# Final_Schematic.net
KiCad netlist of a schematic drawn in EAGLE
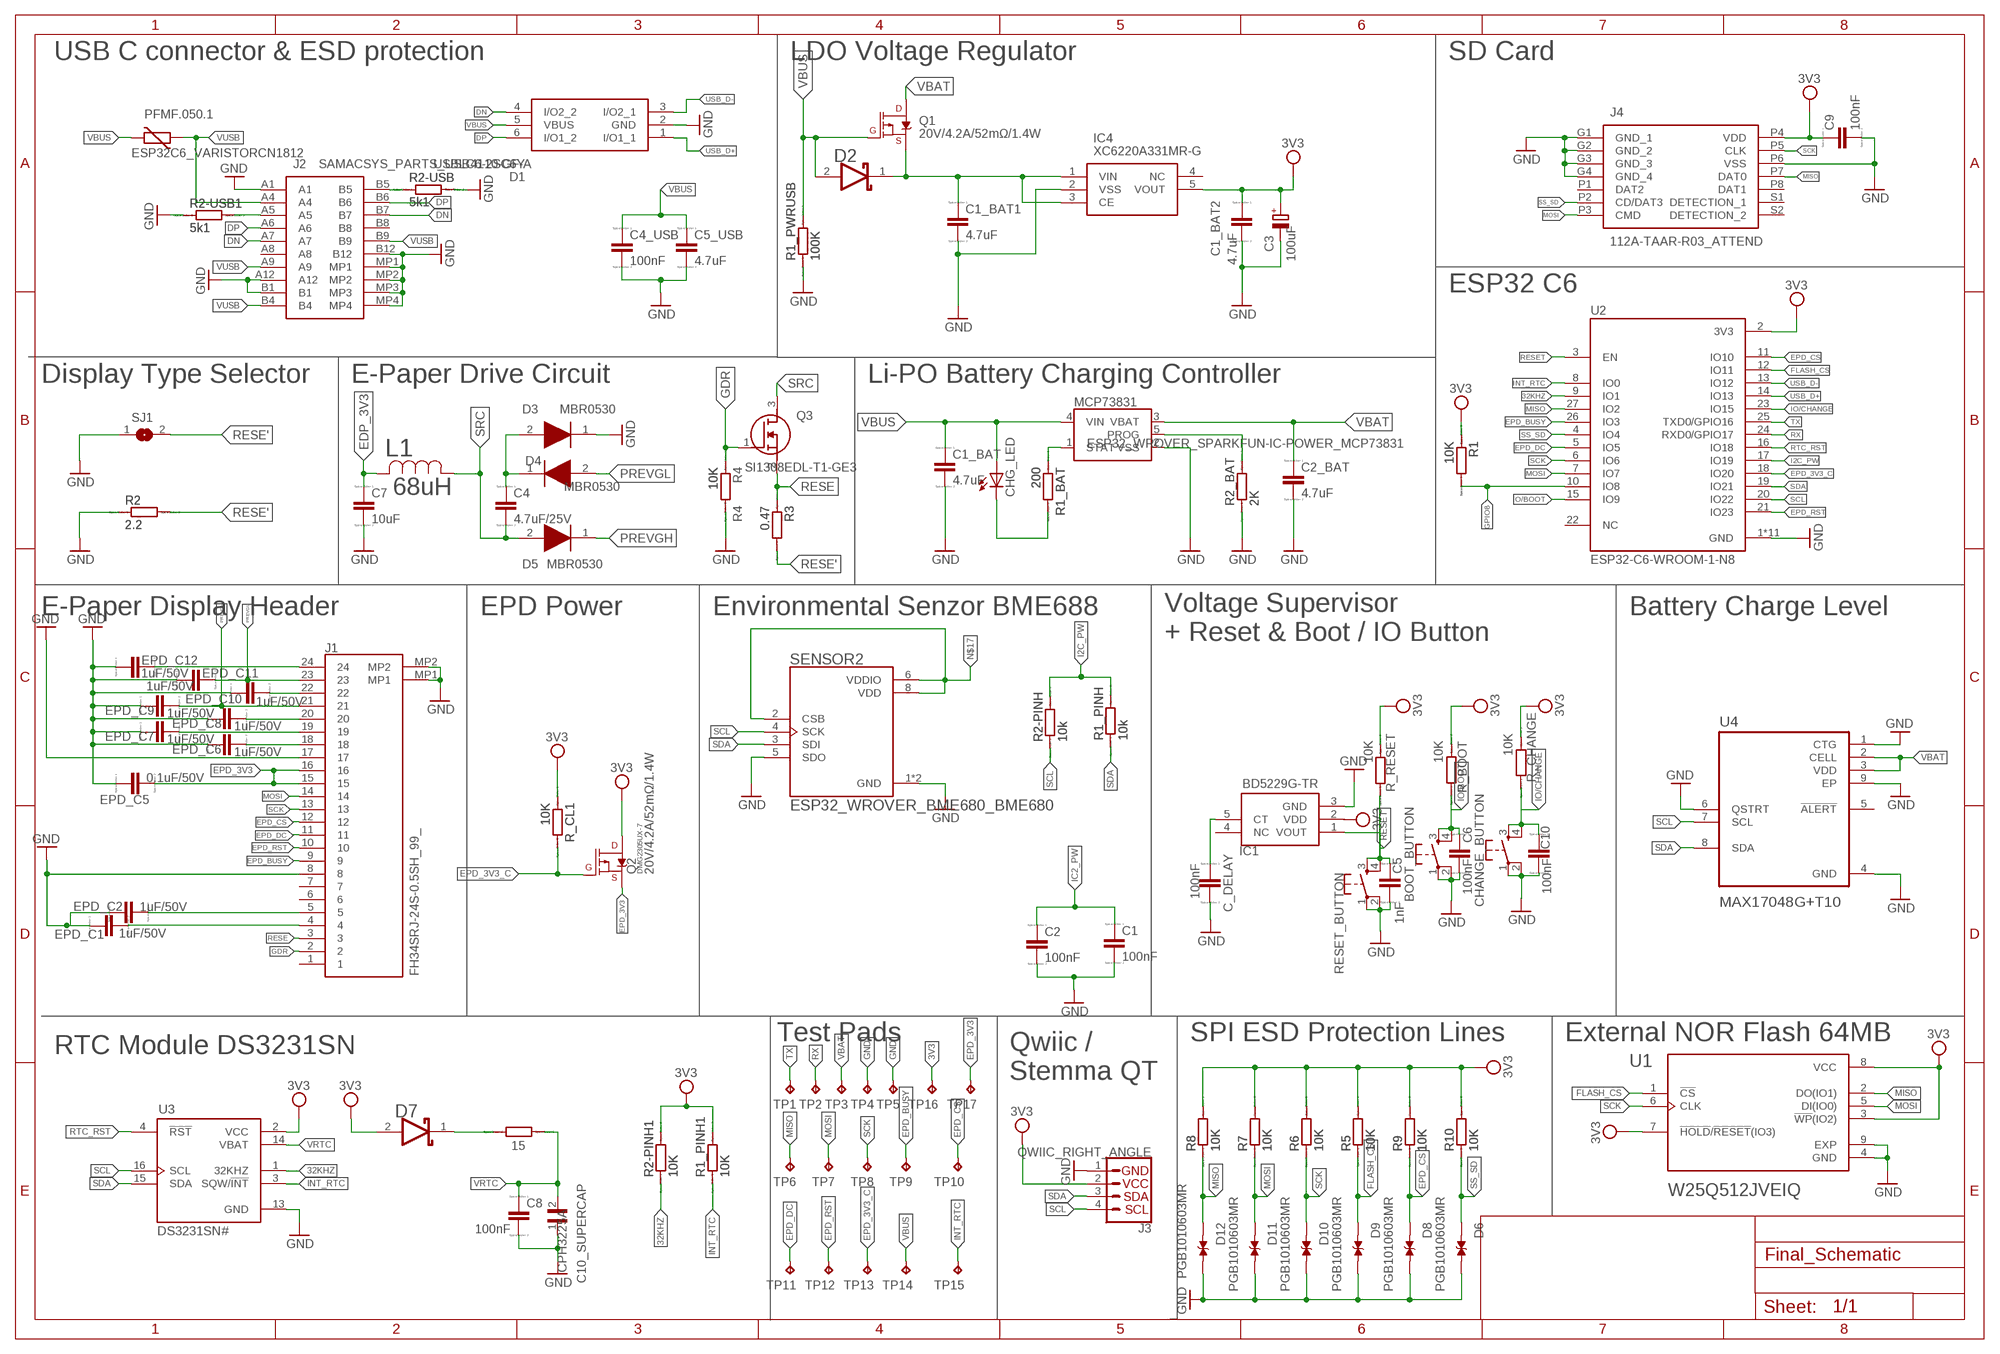
[diagram p0: schematic, sheet 1]

(export (version "E")
  (design (tool "Eeschema 10.0.6"))
  (components
    (comp (ref "BOOT_BUTTON")
      (value "BUTTON_CUSYOMV1")
      (footprint "eagle-import:MYBUTTON")
      (libsource (lib "eagle-import") (part "BUTTON_CUSYOMV1"))
    )
    (comp (ref "C1")
      (value "100nF")
      (footprint "eagle-import:ESP32_WROVER_EAGLE-LTSPICE_C0402")
      (libsource (lib "eagle-import") (part "DeskAssistant v19 v1_vf.HdFh8cW1TheJxZSlz_xEUw_ESP32_WROVER_EAGLE-LTSPICE_CC0402"))
    )
    (comp (ref "C1_BAT")
      (value "4.7uF")
      (footprint "eagle-import:ESP32_WROVER_EAGLE-LTSPICE_C0402")
      (libsource (lib "eagle-import") (part "ESP32_WROVER_EAGLE-LTSPICE_CC0402"))
    )
    (comp (ref "C1_BAT1")
      (value "4.7uF")
      (footprint "eagle-import:ESP32_WROVER_EAGLE-LTSPICE_C0402")
      (libsource (lib "eagle-import") (part "ESP32_WROVER_EAGLE-LTSPICE_CC0402"))
    )
    (comp (ref "C1_BAT2")
      (value "4.7uF")
      (footprint "eagle-import:ESP32_WROVER_EAGLE-LTSPICE_C0402")
      (libsource (lib "eagle-import") (part "ESP32_WROVER_EAGLE-LTSPICE_CC0402"))
    )
    (comp (ref "C2")
      (value "100nF")
      (footprint "eagle-import:ESP32_WROVER_EAGLE-LTSPICE_C0402")
      (libsource (lib "eagle-import") (part "DeskAssistant v19 v1_vf.HdFh8cW1TheJxZSlz_xEUw_ESP32_WROVER_EAGLE-LTSPICE_CC0402"))
    )
    (comp (ref "C2_BAT")
      (value "4.7uF")
      (footprint "eagle-import:ESP32_WROVER_EAGLE-LTSPICE_C0402")
      (libsource (lib "eagle-import") (part "ESP32_WROVER_EAGLE-LTSPICE_CC0402"))
    )
    (comp (ref "C3")
      (value "100uF")
      (footprint "eagle-import:RCL_CT3528")
      (libsource (lib "eagle-import") (part "RCL_CPOL-EUCT3528"))
    )
    (comp (ref "C4")
      (value "4.7uF/25V")
      (footprint "eagle-import:ESP32_WROVER_EAGLE-LTSPICE_C0402")
      (libsource (lib "eagle-import") (part "ESP32_WROVER_EAGLE-LTSPICE_CC0402"))
    )
    (comp (ref "C4_USB")
      (value "100nF")
      (footprint "eagle-import:ESP32_WROVER_EAGLE-LTSPICE_C0402")
      (libsource (lib "eagle-import") (part "ESP32_WROVER_EAGLE-LTSPICE_CC0402"))
    )
    (comp (ref "C5")
      (value "1nF")
      (footprint "eagle-import:EAGLE-LTSPICE_C0402")
      (libsource (lib "eagle-import") (part "EAGLE-LTSPICE_CC0402"))
    )
    (comp (ref "C5_USB")
      (value "4.7uF")
      (footprint "eagle-import:ESP32_WROVER_EAGLE-LTSPICE_C0402")
      (libsource (lib "eagle-import") (part "ESP32_WROVER_EAGLE-LTSPICE_CC0402"))
    )
    (comp (ref "C6")
      (value "100nF")
      (footprint "eagle-import:EAGLE-LTSPICE_C0402")
      (libsource (lib "eagle-import") (part "EAGLE-LTSPICE_CC0402"))
    )
    (comp (ref "C7")
      (value "10uF")
      (footprint "eagle-import:ESP32_WROVER_EAGLE-LTSPICE_C0402")
      (libsource (lib "eagle-import") (part "ESP32_WROVER_EAGLE-LTSPICE_CC0402"))
    )
    (comp (ref "C8")
      (value "100nF")
      (footprint "eagle-import:ESP32_WROVER_EAGLE-LTSPICE_C0402")
      (libsource (lib "eagle-import") (part "ESP32_WROVER_EAGLE-LTSPICE_CC0402"))
    )
    (comp (ref "C9")
      (value "100nF")
      (footprint "eagle-import:ESP32_WROVER_EAGLE-LTSPICE_C0402")
      (libsource (lib "eagle-import") (part "ESP32_WROVER_EAGLE-LTSPICE_CC0402"))
    )
    (comp (ref "C10")
      (value "100nF")
      (footprint "eagle-import:EAGLE-LTSPICE_C0402")
      (libsource (lib "eagle-import") (part "EAGLE-LTSPICE_CC0402"))
    )
    (comp (ref "C10_SUPERCAP")
      (value "CPH3225A")
      (footprint "eagle-import:CAPCP3225X100N")
      (fields (field (name "MF") "Seiko Instruments"))
      (libsource (lib "eagle-import") (part "CPH3225A"))
    )
    (comp (ref "CHANGE_BUTTON")
      (value "BUTTON_CUSYOMV1")
      (footprint "eagle-import:MYBUTTON")
      (libsource (lib "eagle-import") (part "BUTTON_CUSYOMV1"))
    )
    (comp (ref "CHG_LED")
      (value "ADAFRUIT_LEDCHIP-LED0603")
      (footprint "eagle-import:ADAFRUIT_CHIP-LED0603")
      (libsource (lib "eagle-import") (part "ADAFRUIT_LEDCHIP-LED0603"))
    )
    (comp (ref "C_DELAY")
      (value "100nF")
      (footprint "eagle-import:ESP32_WROVER_EAGLE-LTSPICE_C0402")
      (libsource (lib "eagle-import") (part "DeskAssistant v19 v1_vf.HdFh8cW1TheJxZSlz_xEUw_ESP32_WROVER_EAGLE-LTSPICE_CC0402"))
    )
    (comp (ref "D1")
      (value "USBLC6-2SC6Y")
      (footprint "eagle-import:SOT95P280X145-6N")
      (fields (field (name "MF") "STMicroelectronics"))
      (libsource (lib "eagle-import") (part "USBLC6-2SC6Y"))
    )
    (comp (ref "D2")
      (value "ESP32_WROVER_AVX---SD0805S020S1R0_AVX_SD0805S020S1R0_0_0AVX_SD0805S020S1R0_0_0")
      (footprint "eagle-import:ESP32_WROVER_AVX---SD0805S020S1R0_AVX_SD0805S020S1R0_0")
      (fields
        (field (name "DIGIKEY_PART_NUMBER") "478-7800-1-ND")
        (field (name "MF") "AVX")
        (field (name "MOUSER_PART_NUMBER") "581-SD0805S020S1R0")
      )
      (libsource (lib "eagle-import") (part "ESP32_WROVER_AVX---SD0805S020S1R0_AVX_SD0805S020S1R0_0_0AVX_SD0805S020S1R0_0_0"))
    )
    (comp (ref "D3")
      (value "MBR0530")
      (footprint "eagle-import:SOD3716X135N")
      (fields (field (name "MF") "ON Semiconductor"))
      (libsource (lib "eagle-import") (part "MBR0530"))
    )
    (comp (ref "D4")
      (value "MBR0530")
      (footprint "eagle-import:SOD3716X135N")
      (fields (field (name "MF") "ON Semiconductor"))
      (libsource (lib "eagle-import") (part "MBR0530"))
    )
    (comp (ref "D5")
      (value "MBR0530")
      (footprint "eagle-import:SOD3716X135N")
      (fields (field (name "MF") "ON Semiconductor"))
      (libsource (lib "eagle-import") (part "MBR0530"))
    )
    (comp (ref "D6")
      (value "PGB1010603MR")
      (footprint "eagle-import:DIOC1608X36N")
      (fields (field (name "MF") "Littelfuse Inc."))
      (libsource (lib "eagle-import") (part "PGB1010603MR"))
    )
    (comp (ref "D7")
      (value "ESP32_WROVER_AVX---SD0805S020S1R0_AVX_SD0805S020S1R0_0_0AVX_SD0805S020S1R0_0_0")
      (footprint "eagle-import:ESP32_WROVER_AVX---SD0805S020S1R0_AVX_SD0805S020S1R0_0")
      (fields
        (field (name "DIGIKEY_PART_NUMBER") "478-7800-1-ND")
        (field (name "MF") "AVX")
        (field (name "MOUSER_PART_NUMBER") "581-SD0805S020S1R0")
      )
      (libsource (lib "eagle-import") (part "ESP32_WROVER_AVX---SD0805S020S1R0_AVX_SD0805S020S1R0_0_0AVX_SD0805S020S1R0_0_0"))
    )
    (comp (ref "D8")
      (value "PGB1010603MR")
      (footprint "eagle-import:DIOC1608X36N")
      (fields (field (name "MF") "Littelfuse Inc."))
      (libsource (lib "eagle-import") (part "PGB1010603MR"))
    )
    (comp (ref "D9")
      (value "PGB1010603MR")
      (footprint "eagle-import:DIOC1608X36N")
      (fields (field (name "MF") "Littelfuse Inc."))
      (libsource (lib "eagle-import") (part "PGB1010603MR"))
    )
    (comp (ref "D10")
      (value "PGB1010603MR")
      (footprint "eagle-import:DIOC1608X36N")
      (fields (field (name "MF") "Littelfuse Inc."))
      (libsource (lib "eagle-import") (part "PGB1010603MR"))
    )
    (comp (ref "D11")
      (value "PGB1010603MR")
      (footprint "eagle-import:DIOC1608X36N")
      (fields (field (name "MF") "Littelfuse Inc."))
      (libsource (lib "eagle-import") (part "PGB1010603MR"))
    )
    (comp (ref "D12")
      (value "PGB1010603MR")
      (footprint "eagle-import:DIOC1608X36N")
      (fields (field (name "MF") "Littelfuse Inc."))
      (libsource (lib "eagle-import") (part "PGB1010603MR"))
    )
    (comp (ref "EPD_C1")
      (value "1uF/50V")
      (footprint "eagle-import:EAGLE-LTSPICE_C0402")
      (libsource (lib "eagle-import") (part "EAGLE-LTSPICE_CC0402"))
    )
    (comp (ref "EPD_C2")
      (value "1uF/50V")
      (footprint "eagle-import:EAGLE-LTSPICE_C0402")
      (libsource (lib "eagle-import") (part "EAGLE-LTSPICE_CC0402"))
    )
    (comp (ref "EPD_C5")
      (value "0.1uF/50V")
      (footprint "eagle-import:EAGLE-LTSPICE_C0402")
      (libsource (lib "eagle-import") (part "EAGLE-LTSPICE_CC0402"))
    )
    (comp (ref "EPD_C6")
      (value "1uF/50V")
      (footprint "eagle-import:EAGLE-LTSPICE_C0402")
      (libsource (lib "eagle-import") (part "EAGLE-LTSPICE_CC0402"))
    )
    (comp (ref "EPD_C7")
      (value "1uF/50V")
      (footprint "eagle-import:EAGLE-LTSPICE_C0402")
      (libsource (lib "eagle-import") (part "EAGLE-LTSPICE_CC0402"))
    )
    (comp (ref "EPD_C8")
      (value "1uF/50V")
      (footprint "eagle-import:EAGLE-LTSPICE_C0402")
      (libsource (lib "eagle-import") (part "EAGLE-LTSPICE_CC0402"))
    )
    (comp (ref "EPD_C9")
      (value "1uF/50V")
      (footprint "eagle-import:EAGLE-LTSPICE_C0402")
      (libsource (lib "eagle-import") (part "EAGLE-LTSPICE_CC0402"))
    )
    (comp (ref "EPD_C10")
      (value "1uF/50V")
      (footprint "eagle-import:EAGLE-LTSPICE_C0402")
      (libsource (lib "eagle-import") (part "EAGLE-LTSPICE_CC0402"))
    )
    (comp (ref "EPD_C11")
      (value "1uF/50V")
      (footprint "eagle-import:EAGLE-LTSPICE_C0402")
      (libsource (lib "eagle-import") (part "EAGLE-LTSPICE_CC0402"))
    )
    (comp (ref "EPD_C12")
      (value "1uF/50V")
      (footprint "eagle-import:EAGLE-LTSPICE_C0402")
      (libsource (lib "eagle-import") (part "EAGLE-LTSPICE_CC0402"))
    )
    (comp (ref "IC1")
      (value "BD5229G-TR")
      (footprint "eagle-import:SOT95P280X125-5N")
      (fields (field (name "MOUSER_PART_NUMBER") "755-BD5229G-TR"))
      (libsource (lib "eagle-import") (part "BD5229G-TR"))
    )
    (comp (ref "IC4")
      (value "XC6220A331MR-G")
      (footprint "eagle-import:SOT95P280X120-5N")
      (fields (field (name "MOUSER_PART_NUMBER") "865-XC6220A331MR-G"))
      (libsource (lib "eagle-import") (part "XC6220A331MR-G"))
    )
    (comp (ref "J1")
      (value "FH34SRJ-24S-0.5SH_99_")
      (footprint "eagle-import:FH34SRJ24S05SH99")
      (fields
        (field (name "MANUFACTURER_PART_NUMBER") "FH34SRJ-24S-0.5SH(99)")
        (field (name "MOUSER_PART_NUMBER") "798-FH34SRJ24S05SH99")
      )
      (libsource (lib "eagle-import") (part "FH34SRJ-24S-0.5SH_99_"))
    )
    (comp (ref "J2")
      (value "SAMACSYS_PARTS_USB4110-GF-A")
      (footprint "eagle-import:SAMACSYS_PARTS_USB4110GFA")
      (fields
        (field (name "MANUFACTURER_PART_NUMBER") "USB4110-GF-A")
        (field (name "MOUSER_PART_NUMBER") "640-USB4110-GF-A")
      )
      (libsource (lib "eagle-import") (part "SAMACSYS_PARTS_USB4110-GF-A"))
    )
    (comp (ref "J3")
      (value "QWIIC_RIGHT_ANGLE")
      (footprint "eagle-import:JST04_1MM_RA")
      (libsource (lib "eagle-import") (part "QWIIC_CONNECTORJS-1MM"))
    )
    (comp (ref "J4")
      (value "112A-TAAR-R03_ATTEND")
      (footprint "eagle-import:112ATAARR03ATTEND")
      (fields (field (name "MANUFACTURER_PART_NUMBER") "112A-TAAR-R03 ATTEND"))
      (libsource (lib "eagle-import") (part "112A-TAAR-R03_ATTEND"))
    )
    (comp (ref "L1")
      (value "68uH")
      (footprint "eagle-import:IND_4828-WE-TPC_WRE")
      (fields
        (field (name "MANUFACTURER_PART_NUMBER") "744043680")
        (field (name "COPYRIGHT") "Copyright (C) 2024 Ultra Librarian. All rights reserved.")
      )
      (libsource (lib "eagle-import") (part "744043680IND_4828-WE-TPC_WRE"))
    )
    (comp (ref "MCP73831")
      (value "ESP32_WROVER_SPARKFUN-IC-POWER_MCP73831")
      (footprint "eagle-import:ESP32_WROVER_SPARKFUN-IC-POWER_SOT23-5")
      (libsource (lib "eagle-import") (part "ESP32_WROVER_SPARKFUN-IC-POWER_MCP73831"))
    )
    (comp (ref "PFMF.050.1")
      (value "ESP32C6_VARISTORCN1812")
      (footprint "eagle-import:ESP32C6_VARISTOR_CT_CN1812")
      (libsource (lib "eagle-import") (part "ESP32C6_VARISTORCN1812"))
    )
    (comp (ref "Q1")
      (value "20V/4.2A/52mΩ/1.4W")
      (footprint "eagle-import:ESP32_WROVER_SPARKFUN-DISCRETESEMI_SOT23-3")
      (libsource (lib "eagle-import") (part "ESP32_WROVER_SPARKFUN-DISCRETESEMI_MOSFET_PCH-DMG2305UX-7"))
    )
    (comp (ref "Q2")
      (value "20V/4.2A/52mΩ/1.4W")
      (footprint "eagle-import:ESP32_WROVER_SPARKFUN-DISCRETESEMI_SOT23-3")
      (libsource (lib "eagle-import") (part "DeskAssistant v19 v1_vf.HdFh8cW1TheJxZSlz_xEUw_ESP32_WROVER_SPARKFUN-DISCRETESEMI_MOSFET_PCH-DMG2305UX-7"))
    )
    (comp (ref "Q3")
      (value "SI1308EDL-T1-GE3")
      (footprint "eagle-import:SOT65P210X110-3N")
      (fields (field (name "MF") "Vishay Siliconix"))
      (libsource (lib "eagle-import") (part "SI1308EDL-T1-GE3"))
    )
    (comp (ref "R1")
      (value "10K")
      (footprint "eagle-import:ESP32_WROVER_EAGLE-LTSPICE_R0402")
      (libsource (lib "eagle-import") (part "ESP32_WROVER_EAGLE-LTSPICE_RR0402"))
    )
    (comp (ref "R1_BAT")
      (value "200")
      (footprint "eagle-import:ESP32_WROVER_EAGLE-LTSPICE_R0402")
      (libsource (lib "eagle-import") (part "ESP32_WROVER_EAGLE-LTSPICE_RR0402"))
    )
    (comp (ref "R1_PINH")
      (value "10k")
      (footprint "eagle-import:ESP32_WROVER_EAGLE-LTSPICE_R0402")
      (libsource (lib "eagle-import") (part "DeskAssistant v19 v1_vf.HdFh8cW1TheJxZSlz_xEUw_ESP32_WROVER_EAGLE-LTSPICE_RR0402"))
    )
    (comp (ref "R1_PINH1")
      (value "10K")
      (footprint "eagle-import:ESP32_WROVER_EAGLE-LTSPICE_R0402")
      (libsource (lib "eagle-import") (part "ESP32_WROVER_EAGLE-LTSPICE_RR0402"))
    )
    (comp (ref "R1_PWRUSB")
      (value "100K")
      (footprint "eagle-import:ESP32_WROVER_EAGLE-LTSPICE_R0402")
      (libsource (lib "eagle-import") (part "ESP32_WROVER_EAGLE-LTSPICE_RR0402"))
    )
    (comp (ref "R2")
      (value "2.2")
      (footprint "eagle-import:ESP32_WROVER_EAGLE-LTSPICE_R0402")
      (libsource (lib "eagle-import") (part "ESP32_WROVER_EAGLE-LTSPICE_RR0402"))
    )
    (comp (ref "R2-PINH")
      (value "10k")
      (footprint "eagle-import:ESP32_WROVER_EAGLE-LTSPICE_R0402")
      (libsource (lib "eagle-import") (part "DeskAssistant v19 v1_vf.HdFh8cW1TheJxZSlz_xEUw_ESP32_WROVER_EAGLE-LTSPICE_RR0402"))
    )
    (comp (ref "R2-PINH1")
      (value "10K")
      (footprint "eagle-import:ESP32_WROVER_EAGLE-LTSPICE_R0402")
      (libsource (lib "eagle-import") (part "ESP32_WROVER_EAGLE-LTSPICE_RR0402"))
    )
    (comp (ref "R2-USB")
      (value "5k1")
      (footprint "eagle-import:ESP32_WROVER_EAGLE-LTSPICE_R0402")
      (libsource (lib "eagle-import") (part "ESP32_WROVER_EAGLE-LTSPICE_RR0402"))
    )
    (comp (ref "R2-USB1")
      (value "5k1")
      (footprint "eagle-import:ESP32_WROVER_EAGLE-LTSPICE_R0402")
      (libsource (lib "eagle-import") (part "ESP32_WROVER_EAGLE-LTSPICE_RR0402"))
    )
    (comp (ref "R2_BAT")
      (value "2K")
      (footprint "eagle-import:ESP32_WROVER_EAGLE-LTSPICE_R0402")
      (libsource (lib "eagle-import") (part "ESP32_WROVER_EAGLE-LTSPICE_RR0402"))
    )
    (comp (ref "R3")
      (value "0.47")
      (footprint "eagle-import:ESP32_WROVER_EAGLE-LTSPICE_R0402")
      (libsource (lib "eagle-import") (part "ESP32_WROVER_EAGLE-LTSPICE_RR0402"))
    )
    (comp (ref "R4")
      (value "10K")
      (footprint "eagle-import:ESP32_WROVER_EAGLE-LTSPICE_R0402")
      (libsource (lib "eagle-import") (part "ESP32_WROVER_EAGLE-LTSPICE_RR0402"))
    )
    (comp (ref "R5")
      (value "10K")
      (footprint "eagle-import:ESP32_WROVER_EAGLE-LTSPICE_R0402")
      (libsource (lib "eagle-import") (part "ESP32_WROVER_EAGLE-LTSPICE_RR0402"))
    )
    (comp (ref "R6")
      (value "10K")
      (footprint "eagle-import:ESP32_WROVER_EAGLE-LTSPICE_R0402")
      (libsource (lib "eagle-import") (part "ESP32_WROVER_EAGLE-LTSPICE_RR0402"))
    )
    (comp (ref "R7")
      (value "10K")
      (footprint "eagle-import:ESP32_WROVER_EAGLE-LTSPICE_R0402")
      (libsource (lib "eagle-import") (part "ESP32_WROVER_EAGLE-LTSPICE_RR0402"))
    )
    (comp (ref "R8")
      (value "10K")
      (footprint "eagle-import:ESP32_WROVER_EAGLE-LTSPICE_R0402")
      (libsource (lib "eagle-import") (part "ESP32_WROVER_EAGLE-LTSPICE_RR0402"))
    )
    (comp (ref "R9")
      (value "10K")
      (footprint "eagle-import:ESP32_WROVER_EAGLE-LTSPICE_R0402")
      (libsource (lib "eagle-import") (part "ESP32_WROVER_EAGLE-LTSPICE_RR0402"))
    )
    (comp (ref "R10")
      (value "10K")
      (footprint "eagle-import:ESP32_WROVER_EAGLE-LTSPICE_R0402")
      (libsource (lib "eagle-import") (part "ESP32_WROVER_EAGLE-LTSPICE_RR0402"))
    )
    (comp (ref "RESET_BUTTON")
      (value "BUTTON_CUSYOMV1")
      (footprint "eagle-import:MYBUTTON")
      (libsource (lib "eagle-import") (part "BUTTON_CUSYOMV1"))
    )
    (comp (ref "R_BOOT")
      (value "10K")
      (footprint "eagle-import:ESP32_WROVER_EAGLE-LTSPICE_R0402")
      (libsource (lib "eagle-import") (part "DeskAssistant v19 v1_vf.HdFh8cW1TheJxZSlz_xEUw_ESP32_WROVER_EAGLE-LTSPICE_RR0402"))
    )
    (comp (ref "R_CAPACITOR")
      (value "15")
      (footprint "eagle-import:ESP32_WROVER_EAGLE-LTSPICE_R0402")
      (libsource (lib "eagle-import") (part "ESP32_WROVER_EAGLE-LTSPICE_RR0402"))
    )
    (comp (ref "R_CHANGE")
      (value "10K")
      (footprint "eagle-import:ESP32_WROVER_EAGLE-LTSPICE_R0402")
      (libsource (lib "eagle-import") (part "DeskAssistant v19 v1_vf.HdFh8cW1TheJxZSlz_xEUw_ESP32_WROVER_EAGLE-LTSPICE_RR0402"))
    )
    (comp (ref "R_CL1")
      (value "10K")
      (footprint "eagle-import:ESP32_WROVER_EAGLE-LTSPICE_R0402")
      (libsource (lib "eagle-import") (part "ESP32_WROVER_EAGLE-LTSPICE_RR0402"))
    )
    (comp (ref "R_RESET")
      (value "10K")
      (footprint "eagle-import:ESP32_WROVER_EAGLE-LTSPICE_R0402")
      (libsource (lib "eagle-import") (part "DeskAssistant v19 v1_vf.HdFh8cW1TheJxZSlz_xEUw_ESP32_WROVER_EAGLE-LTSPICE_RR0402"))
    )
    (comp (ref "SENSOR2")
      (value "ESP32_WROVER_BME680_BME680")
      (footprint "eagle-import:ESP32_WROVER_BME680_PSON80P300X300X100-8N")
      (fields (field (name "MF") "Bosch Sensortec") (field (name "MP") "BME680"))
      (libsource (lib "eagle-import") (part "ESP32_WROVER_BME680_BME680"))
    )
    (comp (ref "SJ1") (value "SJ") (footprint "eagle-import:SJ") (libsource (lib "eagle-import") (part "SJ")))
    (comp (ref "TP1")
      (value "TPTP20R")
      (footprint "eagle-import:TP20R")
      (libsource (lib "eagle-import") (part "TPTP20R"))
    )
    (comp (ref "TP2")
      (value "TPTP20R")
      (footprint "eagle-import:TP20R")
      (libsource (lib "eagle-import") (part "TPTP20R"))
    )
    (comp (ref "TP3")
      (value "TPTP20R")
      (footprint "eagle-import:TP20R")
      (libsource (lib "eagle-import") (part "TPTP20R"))
    )
    (comp (ref "TP4")
      (value "TPTP20R")
      (footprint "eagle-import:TP20R")
      (libsource (lib "eagle-import") (part "TPTP20R"))
    )
    (comp (ref "TP5")
      (value "TPTP20R")
      (footprint "eagle-import:TP20R")
      (libsource (lib "eagle-import") (part "TPTP20R"))
    )
    (comp (ref "TP6")
      (value "TPTP20R")
      (footprint "eagle-import:TP20R")
      (libsource (lib "eagle-import") (part "TPTP20R"))
    )
    (comp (ref "TP7")
      (value "TPTP20R")
      (footprint "eagle-import:TP20R")
      (libsource (lib "eagle-import") (part "TPTP20R"))
    )
    (comp (ref "TP8")
      (value "TPTP20R")
      (footprint "eagle-import:TP20R")
      (libsource (lib "eagle-import") (part "TPTP20R"))
    )
    (comp (ref "TP9")
      (value "TPTP20R")
      (footprint "eagle-import:TP20R")
      (libsource (lib "eagle-import") (part "TPTP20R"))
    )
    (comp (ref "TP10")
      (value "TPTP20R")
      (footprint "eagle-import:TP20R")
      (libsource (lib "eagle-import") (part "TPTP20R"))
    )
    (comp (ref "TP11")
      (value "TPTP20R")
      (footprint "eagle-import:TP20R")
      (libsource (lib "eagle-import") (part "TPTP20R"))
    )
    (comp (ref "TP12")
      (value "TPTP20R")
      (footprint "eagle-import:TP20R")
      (libsource (lib "eagle-import") (part "TPTP20R"))
    )
    (comp (ref "TP13")
      (value "TPTP20R")
      (footprint "eagle-import:TP20R")
      (libsource (lib "eagle-import") (part "TPTP20R"))
    )
    (comp (ref "TP14")
      (value "TPTP20R")
      (footprint "eagle-import:TP20R")
      (libsource (lib "eagle-import") (part "TPTP20R"))
    )
    (comp (ref "TP15")
      (value "TPTP20R")
      (footprint "eagle-import:TP20R")
      (libsource (lib "eagle-import") (part "TPTP20R"))
    )
    (comp (ref "TP16")
      (value "TPTP20R")
      (footprint "eagle-import:TP20R")
      (libsource (lib "eagle-import") (part "TPTP20R"))
    )
    (comp (ref "TP17")
      (value "TPTP20R")
      (footprint "eagle-import:TP20R")
      (libsource (lib "eagle-import") (part "TPTP20R"))
    )
    (comp (ref "U1")
      (value "W25Q512JVEIQ")
      (footprint "eagle-import:SON127P600X800X80-9N")
      (fields (field (name "MF") "Winbond Electronics"))
      (libsource (lib "eagle-import") (part "W25Q512JVEIQ"))
    )
    (comp (ref "U2")
      (value "ESP32-C6-WROOM-1-N8")
      (footprint "eagle-import:XCVR_ESP32-C6-WROOM-1-N8")
      (fields (field (name "MF") "Espressif Systems"))
      (libsource (lib "eagle-import") (part "ESP32-C6-WROOM-1-N8"))
    )
    (comp (ref "U3")
      (value "DS3231SN#")
      (footprint "eagle-import:SOIC127P1032X265-16N")
      (fields (field (name "MF") "Analog Devices"))
      (libsource (lib "eagle-import") (part "DS3231SN#"))
    )
    (comp (ref "U4")
      (value "MAX17048G+T10")
      (footprint "eagle-import:SON50P200X200X80-9N")
      (fields (field (name "MF") "Analog Devices"))
      (libsource (lib "eagle-import") (part "MAX17048G+T10"))
    )
  )
  (nets
    (net (code "1") (name "3V3") (class "Default")
      (node (ref "C1_BAT2") (pin "1") (pinfunction "1_1") (pintype "passive"))
      (node (ref "C3") (pin "+") (pinfunction "+_+") (pintype "passive"))
      (node (ref "C9") (pin "1") (pinfunction "1_1") (pintype "passive"))
      (node (ref "D7") (pin "2") (pinfunction "ANODE_2") (pintype "bidirectional"))
      (node (ref "IC4") (pin "5") (pinfunction "VOUT_5") (pintype "bidirectional"))
      (node (ref "J3") (pin "2") (pinfunction "2_2") (pintype "power_in"))
      (node (ref "J4") (pin "P4") (pinfunction "VDD_P4") (pintype "bidirectional"))
      (node (ref "Q2") (pin "3") (pinfunction "D_3") (pintype "bidirectional"))
      (node (ref "R1") (pin "1") (pinfunction "1_1") (pintype "passive"))
      (node (ref "R10") (pin "2") (pinfunction "2_2") (pintype "passive"))
      (node (ref "R1_PINH1") (pin "2") (pinfunction "2_2") (pintype "passive"))
      (node (ref "R2-PINH1") (pin "2") (pinfunction "2_2") (pintype "passive"))
      (node (ref "R5") (pin "2") (pinfunction "2_2") (pintype "passive"))
      (node (ref "R6") (pin "2") (pinfunction "2_2") (pintype "passive"))
      (node (ref "R7") (pin "2") (pinfunction "2_2") (pintype "passive"))
      (node (ref "R8") (pin "2") (pinfunction "2_2") (pintype "passive"))
      (node (ref "R9") (pin "2") (pinfunction "2_2") (pintype "passive"))
      (node (ref "R_BOOT") (pin "2") (pinfunction "2_2") (pintype "passive"))
      (node (ref "R_CHANGE") (pin "2") (pinfunction "2_2") (pintype "passive"))
      (node (ref "R_CL1") (pin "1") (pinfunction "1_1") (pintype "passive"))
      (node (ref "R_RESET") (pin "2") (pinfunction "2_2") (pintype "passive"))
      (node (ref "TP16") (pin "TP") (pinfunction "TP_TP") (pintype "input"))
      (node (ref "U1") (pin "3") (pinfunction "~{WP}(IO2)_3") (pintype "bidirectional"))
      (node (ref "U1") (pin "7") (pinfunction "~{HOLD}/~{RESET}(IO3)_7") (pintype "bidirectional"))
      (node (ref "U1") (pin "8") (pinfunction "VCC_8") (pintype "power_in"))
      (node (ref "U2") (pin "2") (pinfunction "3V3_2") (pintype "power_in"))
      (node (ref "U3") (pin "2") (pinfunction "VCC_2") (pintype "power_in"))
    )
    (net (code "2") (name "32KHZ") (class "Default")
      (node (ref "R2-PINH1") (pin "1") (pinfunction "1_1") (pintype "passive"))
      (node (ref "U2") (pin "9") (pinfunction "IO1_9") (pintype "bidirectional"))
      (node (ref "U3") (pin "1") (pinfunction "32KHZ_1") (pintype "output"))
    )
    (net (code "3") (name "DN") (class "Default")
      (node (ref "D1") (pin "4") (pinfunction "I/O2_2_4") (pintype "bidirectional"))
      (node (ref "J2") (pin "A7") (pinfunction "A7_A7") (pintype "bidirectional"))
      (node (ref "J2") (pin "B7") (pinfunction "B7_B7") (pintype "bidirectional"))
    )
    (net (code "4") (name "DP") (class "Default")
      (node (ref "D1") (pin "6") (pinfunction "I/O1_2_6") (pintype "bidirectional"))
      (node (ref "J2") (pin "A6") (pinfunction "A6_A6") (pintype "bidirectional"))
      (node (ref "J2") (pin "B6") (pinfunction "B6_B6") (pintype "bidirectional"))
    )
    (net (code "5") (name "EDP_3V3") (class "Default")
      (node (ref "C7") (pin "1") (pinfunction "1_1") (pintype "passive"))
      (node (ref "L1") (pin "2") (pinfunction "2_2") (pintype "passive"))
    )
    (net (code "6") (name "EPD_3V3") (class "Default")
      (node (ref "EPD_C5") (pin "2") (pinfunction "2_2") (pintype "passive"))
      (node (ref "J1") (pin "15") (pinfunction "15_15") (pintype "bidirectional"))
      (node (ref "J1") (pin "16") (pinfunction "16_16") (pintype "bidirectional"))
      (node (ref "Q2") (pin "2") (pinfunction "S_2") (pintype "bidirectional"))
      (node (ref "TP17") (pin "TP") (pinfunction "TP_TP") (pintype "input"))
    )
    (net (code "7") (name "EPD_3V3_C") (class "Default")
      (node (ref "Q2") (pin "1") (pinfunction "G_1") (pintype "bidirectional"))
      (node (ref "R_CL1") (pin "2") (pinfunction "2_2") (pintype "passive"))
      (node (ref "TP13") (pin "TP") (pinfunction "TP_TP") (pintype "input"))
      (node (ref "U2") (pin "18") (pinfunction "IO20_18") (pintype "bidirectional"))
    )
    (net (code "8") (name "EPD_BUSY") (class "Default")
      (node (ref "J1") (pin "9") (pinfunction "9_9") (pintype "bidirectional"))
      (node (ref "TP9") (pin "TP") (pinfunction "TP_TP") (pintype "input"))
      (node (ref "U2") (pin "26") (pinfunction "IO3_26") (pintype "bidirectional"))
    )
    (net (code "9") (name "EPD_CS") (class "Default")
      (node (ref "D8") (pin "1") (pinfunction "1_1") (pintype "passive"))
      (node (ref "J1") (pin "12") (pinfunction "12_12") (pintype "bidirectional"))
      (node (ref "R9") (pin "1") (pinfunction "1_1") (pintype "passive"))
      (node (ref "TP10") (pin "TP") (pinfunction "TP_TP") (pintype "input"))
      (node (ref "U2") (pin "11") (pinfunction "IO10_11") (pintype "bidirectional"))
    )
    (net (code "10") (name "EPD_DC") (class "Default")
      (node (ref "J1") (pin "11") (pinfunction "11_11") (pintype "bidirectional"))
      (node (ref "TP11") (pin "TP") (pinfunction "TP_TP") (pintype "input"))
      (node (ref "U2") (pin "5") (pinfunction "IO5_5") (pintype "bidirectional"))
    )
    (net (code "11") (name "EPD_RST") (class "Default")
      (node (ref "J1") (pin "10") (pinfunction "10_10") (pintype "bidirectional"))
      (node (ref "TP12") (pin "TP") (pinfunction "TP_TP") (pintype "input"))
      (node (ref "U2") (pin "21") (pinfunction "IO23_21") (pintype "bidirectional"))
    )
    (net (code "12") (name "FLASH_CS") (class "Default")
      (node (ref "D9") (pin "1") (pinfunction "1_1") (pintype "passive"))
      (node (ref "R5") (pin "1") (pinfunction "1_1") (pintype "passive"))
      (node (ref "U1") (pin "1") (pinfunction "~{CS}_1") (pintype "input"))
      (node (ref "U2") (pin "12") (pinfunction "IO11_12") (pintype "bidirectional"))
    )
    (net (code "13") (name "GDR") (class "Default")
      (node (ref "J1") (pin "2") (pinfunction "2_2") (pintype "bidirectional"))
      (node (ref "Q3") (pin "1") (pinfunction "G_1") (pintype "bidirectional"))
      (node (ref "R4") (pin "1") (pinfunction "1_1") (pintype "passive"))
    )
    (net (code "14") (name "GND") (class "Default")
      (node (ref "BOOT_BUTTON") (pin "1") (pinfunction "1_1") (pintype "passive"))
      (node (ref "BOOT_BUTTON") (pin "2") (pinfunction "2_2") (pintype "passive"))
      (node (ref "C1") (pin "2") (pinfunction "2_2") (pintype "passive"))
      (node (ref "C10") (pin "2") (pinfunction "2_2") (pintype "passive"))
      (node (ref "C10_SUPERCAP") (pin "1") (pinfunction "1_1") (pintype "passive"))
      (node (ref "C1_BAT") (pin "2") (pinfunction "2_2") (pintype "passive"))
      (node (ref "C1_BAT1") (pin "2") (pinfunction "2_2") (pintype "passive"))
      (node (ref "C1_BAT2") (pin "2") (pinfunction "2_2") (pintype "passive"))
      (node (ref "C2") (pin "2") (pinfunction "2_2") (pintype "passive"))
      (node (ref "C2_BAT") (pin "2") (pinfunction "2_2") (pintype "passive"))
      (node (ref "C3") (pin "-") (pinfunction "-_-") (pintype "passive"))
      (node (ref "C4_USB") (pin "2") (pinfunction "2_2") (pintype "passive"))
      (node (ref "C5") (pin "2") (pinfunction "2_2") (pintype "passive"))
      (node (ref "C5_USB") (pin "2") (pinfunction "2_2") (pintype "passive"))
      (node (ref "C6") (pin "2") (pinfunction "2_2") (pintype "passive"))
      (node (ref "C7") (pin "2") (pinfunction "2_2") (pintype "passive"))
      (node (ref "C8") (pin "2") (pinfunction "2_2") (pintype "passive"))
      (node (ref "C9") (pin "2") (pinfunction "2_2") (pintype "passive"))
      (node (ref "CHANGE_BUTTON") (pin "1") (pinfunction "1_1") (pintype "passive"))
      (node (ref "CHANGE_BUTTON") (pin "2") (pinfunction "2_2") (pintype "passive"))
      (node (ref "C_DELAY") (pin "2") (pinfunction "2_2") (pintype "passive"))
      (node (ref "D1") (pin "2") (pinfunction "GND_2") (pintype "bidirectional"))
      (node (ref "D10") (pin "2") (pinfunction "2_2") (pintype "passive"))
      (node (ref "D11") (pin "2") (pinfunction "2_2") (pintype "passive"))
      (node (ref "D12") (pin "2") (pinfunction "2_2") (pintype "passive"))
      (node (ref "D3") (pin "1") (pinfunction "K_1") (pintype "bidirectional"))
      (node (ref "D6") (pin "2") (pinfunction "2_2") (pintype "passive"))
      (node (ref "D8") (pin "2") (pinfunction "2_2") (pintype "passive"))
      (node (ref "D9") (pin "2") (pinfunction "2_2") (pintype "passive"))
      (node (ref "EPD_C1") (pin "1") (pinfunction "1_1") (pintype "passive"))
      (node (ref "EPD_C10") (pin "1") (pinfunction "1_1") (pintype "passive"))
      (node (ref "EPD_C11") (pin "1") (pinfunction "1_1") (pintype "passive"))
      (node (ref "EPD_C12") (pin "1") (pinfunction "1_1") (pintype "passive"))
      (node (ref "EPD_C2") (pin "1") (pinfunction "1_1") (pintype "passive"))
      (node (ref "EPD_C5") (pin "1") (pinfunction "1_1") (pintype "passive"))
      (node (ref "EPD_C6") (pin "1") (pinfunction "1_1") (pintype "passive"))
      (node (ref "EPD_C7") (pin "1") (pinfunction "1_1") (pintype "passive"))
      (node (ref "EPD_C8") (pin "1") (pinfunction "1_1") (pintype "passive"))
      (node (ref "EPD_C9") (pin "1") (pinfunction "1_1") (pintype "passive"))
      (node (ref "IC1") (pin "3") (pinfunction "GND_3") (pintype "bidirectional"))
      (node (ref "IC4") (pin "2") (pinfunction "VSS_2") (pintype "bidirectional"))
      (node (ref "J1") (pin "17") (pinfunction "17_17") (pintype "bidirectional"))
      (node (ref "J1") (pin "8") (pinfunction "8_8") (pintype "bidirectional"))
      (node (ref "J1") (pin "MP1") (pinfunction "MP1_MP1") (pintype "bidirectional"))
      (node (ref "J1") (pin "MP2") (pinfunction "MP2_MP2") (pintype "bidirectional"))
      (node (ref "J2") (pin "A1") (pinfunction "A1_A1") (pintype "bidirectional"))
      (node (ref "J2") (pin "A12") (pinfunction "A12_A12") (pintype "bidirectional"))
      (node (ref "J2") (pin "B1") (pinfunction "B1_B1") (pintype "bidirectional"))
      (node (ref "J2") (pin "B12") (pinfunction "B12_B12") (pintype "bidirectional"))
      (node (ref "J2") (pin "MP1") (pinfunction "MP1_MP1") (pintype "bidirectional"))
      (node (ref "J2") (pin "MP2") (pinfunction "MP2_MP2") (pintype "bidirectional"))
      (node (ref "J2") (pin "MP3") (pinfunction "MP3_MP3") (pintype "bidirectional"))
      (node (ref "J2") (pin "MP4") (pinfunction "MP4_MP4") (pintype "bidirectional"))
      (node (ref "J3") (pin "1") (pinfunction "1_1") (pintype "power_in"))
      (node (ref "J4") (pin "G1") (pinfunction "GND_1_G1") (pintype "bidirectional"))
      (node (ref "J4") (pin "G2") (pinfunction "GND_2_G2") (pintype "bidirectional"))
      (node (ref "J4") (pin "G3") (pinfunction "GND_3_G3") (pintype "bidirectional"))
      (node (ref "J4") (pin "G4") (pinfunction "GND_4_G4") (pintype "bidirectional"))
      (node (ref "J4") (pin "P6") (pinfunction "VSS_P6") (pintype "bidirectional"))
      (node (ref "MCP73831") (pin "2") (pinfunction "VSS_2") (pintype "power_in"))
      (node (ref "R1_PWRUSB") (pin "1") (pinfunction "1_1") (pintype "passive"))
      (node (ref "R2") (pin "1") (pinfunction "1_1") (pintype "passive"))
      (node (ref "R2-USB") (pin "2") (pinfunction "2_2") (pintype "passive"))
      (node (ref "R2-USB1") (pin "1") (pinfunction "1_1") (pintype "passive"))
      (node (ref "R2_BAT") (pin "1") (pinfunction "1_1") (pintype "passive"))
      (node (ref "R4") (pin "2") (pinfunction "2_2") (pintype "passive"))
      (node (ref "RESET_BUTTON") (pin "1") (pinfunction "1_1") (pintype "passive"))
      (node (ref "RESET_BUTTON") (pin "2") (pinfunction "2_2") (pintype "passive"))
      (node (ref "SENSOR2") (pin "1") (pinfunction "GND_1") (pintype "power_in"))
      (node (ref "SENSOR2") (pin "5") (pinfunction "SDO_5") (pintype "bidirectional"))
      (node (ref "SENSOR2") (pin "7") (pinfunction "GND_7") (pintype "power_in"))
      (node (ref "SJ1") (pin "1") (pinfunction "1_1") (pintype "passive"))
      (node (ref "TP4") (pin "TP") (pinfunction "TP_TP") (pintype "input"))
      (node (ref "TP5") (pin "TP") (pinfunction "TP_TP") (pintype "input"))
      (node (ref "U1") (pin "4") (pinfunction "GND_4") (pintype "power_in"))
      (node (ref "U1") (pin "9") (pinfunction "EXP_9") (pintype "passive"))
      (node (ref "U2") (pin "1") (pinfunction "GND_1") (pintype "power_in"))
      (node (ref "U2") (pin "28") (pinfunction "GND_28") (pintype "power_in"))
      (node (ref "U2") (pin "29_1") (pinfunction "GND_29_1") (pintype "power_in"))
      (node (ref "U2") (pin "29_2") (pinfunction "GND_29_2") (pintype "power_in"))
      (node (ref "U2") (pin "29_3") (pinfunction "GND_29_3") (pintype "power_in"))
      (node (ref "U2") (pin "29_4") (pinfunction "GND_29_4") (pintype "power_in"))
      (node (ref "U2") (pin "29_5") (pinfunction "GND_29_5") (pintype "power_in"))
      (node (ref "U2") (pin "29_6") (pinfunction "GND_29_6") (pintype "power_in"))
      (node (ref "U2") (pin "29_7") (pinfunction "GND_29_7") (pintype "power_in"))
      (node (ref "U2") (pin "29_8") (pinfunction "GND_29_8") (pintype "power_in"))
      (node (ref "U2") (pin "29_9") (pinfunction "GND_29_9") (pintype "power_in"))
      (node (ref "U3") (pin "13") (pinfunction "GND_13") (pintype "power_in"))
      (node (ref "U4") (pin "1") (pinfunction "CTG_1") (pintype "power_in"))
      (node (ref "U4") (pin "4") (pinfunction "GND_4") (pintype "power_in"))
      (node (ref "U4") (pin "6") (pinfunction "QSTRT_6") (pintype "input"))
      (node (ref "U4") (pin "9") (pinfunction "EP_9") (pintype "power_in"))
    )
    (net (code "15") (name "GPIO8") (class "Default")
      (node (ref "R1") (pin "2") (pinfunction "2_2") (pintype "passive"))
      (node (ref "U2") (pin "10") (pinfunction "IO8_10") (pintype "bidirectional"))
    )
    (net (code "16") (name "I2C_PW") (class "Default")
      (node (ref "R1_PINH") (pin "2") (pinfunction "2_2") (pintype "passive"))
      (node (ref "R2-PINH") (pin "2") (pinfunction "2_2") (pintype "passive"))
      (node (ref "U2") (pin "17") (pinfunction "IO19_17") (pintype "bidirectional"))
    )
    (net (code "17") (name "IC2_PW") (class "Default")
      (node (ref "C1") (pin "1") (pinfunction "1_1") (pintype "passive"))
      (node (ref "C2") (pin "1") (pinfunction "1_1") (pintype "passive"))
    )
    (net (code "18") (name "INT_RTC") (class "Default")
      (node (ref "R1_PINH1") (pin "1") (pinfunction "1_1") (pintype "passive"))
      (node (ref "TP15") (pin "TP") (pinfunction "TP_TP") (pintype "input"))
      (node (ref "U2") (pin "8") (pinfunction "IO0_8") (pintype "bidirectional"))
      (node (ref "U3") (pin "3") (pinfunction "SQW/~{INT}_3") (pintype "output"))
    )
    (net (code "19") (name "IO{slash}BOOT") (class "Default")
      (node (ref "BOOT_BUTTON") (pin "3") (pinfunction "3_3") (pintype "passive"))
      (node (ref "BOOT_BUTTON") (pin "4") (pinfunction "4_4") (pintype "passive"))
      (node (ref "C6") (pin "1") (pinfunction "1_1") (pintype "passive"))
      (node (ref "R_BOOT") (pin "1") (pinfunction "1_1") (pintype "passive"))
      (node (ref "U2") (pin "15") (pinfunction "IO9_15") (pintype "bidirectional"))
    )
    (net (code "20") (name "IO{slash}CHANGE") (class "Default")
      (node (ref "C10") (pin "1") (pinfunction "1_1") (pintype "passive"))
      (node (ref "CHANGE_BUTTON") (pin "3") (pinfunction "3_3") (pintype "passive"))
      (node (ref "CHANGE_BUTTON") (pin "4") (pinfunction "4_4") (pintype "passive"))
      (node (ref "R_CHANGE") (pin "1") (pinfunction "1_1") (pintype "passive"))
      (node (ref "U2") (pin "23") (pinfunction "IO15_23") (pintype "bidirectional"))
    )
    (net (code "21") (name "MISO") (class "Default")
      (node (ref "D12") (pin "1") (pinfunction "1_1") (pintype "passive"))
      (node (ref "J4") (pin "P7") (pinfunction "DAT0_P7") (pintype "bidirectional"))
      (node (ref "R8") (pin "1") (pinfunction "1_1") (pintype "passive"))
      (node (ref "TP6") (pin "TP") (pinfunction "TP_TP") (pintype "input"))
      (node (ref "U1") (pin "2") (pinfunction "DO(IO1)_2") (pintype "bidirectional"))
      (node (ref "U2") (pin "27") (pinfunction "IO2_27") (pintype "bidirectional"))
    )
    (net (code "22") (name "MOSI") (class "Default")
      (node (ref "D11") (pin "1") (pinfunction "1_1") (pintype "passive"))
      (node (ref "J1") (pin "14") (pinfunction "14_14") (pintype "bidirectional"))
      (node (ref "J4") (pin "P3") (pinfunction "CMD_P3") (pintype "bidirectional"))
      (node (ref "R7") (pin "1") (pinfunction "1_1") (pintype "passive"))
      (node (ref "TP7") (pin "TP") (pinfunction "TP_TP") (pintype "input"))
      (node (ref "U1") (pin "5") (pinfunction "DI(IO0)_5") (pintype "bidirectional"))
      (node (ref "U2") (pin "7") (pinfunction "IO7_7") (pintype "bidirectional"))
    )
    (net (code "23") (name "N$17") (class "Default")
      (node (ref "SENSOR2") (pin "2") (pinfunction "CSB_2") (pintype "input"))
      (node (ref "SENSOR2") (pin "6") (pinfunction "VDDIO_6") (pintype "power_in"))
      (node (ref "SENSOR2") (pin "8") (pinfunction "VDD_8") (pintype "power_in"))
    )
    (net (code "24") (name "Net-(CHG_LED-PadC)") (class "Default")
      (node (ref "CHG_LED") (pin "C") (pinfunction "C_C") (pintype "passive"))
      (node (ref "R1_BAT") (pin "2") (pinfunction "2_2") (pintype "passive"))
    )
    (net (code "25") (name "Net-(D2-CATHODE)") (class "Default")
      (node (ref "C1_BAT1") (pin "1") (pinfunction "1_1") (pintype "passive"))
      (node (ref "D2") (pin "1") (pinfunction "CATHODE_1") (pintype "bidirectional"))
      (node (ref "IC4") (pin "1") (pinfunction "VIN_1") (pintype "bidirectional"))
      (node (ref "IC4") (pin "3") (pinfunction "CE_3") (pintype "bidirectional"))
      (node (ref "Q1") (pin "2") (pinfunction "S_2") (pintype "bidirectional"))
    )
    (net (code "26") (name "Net-(D3-A)") (class "Default")
      (node (ref "C4") (pin "1") (pinfunction "1_1") (pintype "passive"))
      (node (ref "D3") (pin "2") (pinfunction "A_2") (pintype "bidirectional"))
      (node (ref "D4") (pin "1") (pinfunction "K_1") (pintype "bidirectional"))
    )
    (net (code "27") (name "Net-(D7-CATHODE)") (class "Default")
      (node (ref "D7") (pin "1") (pinfunction "CATHODE_1") (pintype "bidirectional"))
      (node (ref "R_CAPACITOR") (pin "2") (pinfunction "2_2") (pintype "passive"))
    )
    (net (code "28") (name "Net-(EPD_C1-Pad2)") (class "Default")
      (node (ref "EPD_C1") (pin "2") (pinfunction "2_2") (pintype "passive"))
      (node (ref "J1") (pin "4") (pinfunction "4_4") (pintype "bidirectional"))
    )
    (net (code "29") (name "Net-(EPD_C2-Pad2)") (class "Default")
      (node (ref "EPD_C2") (pin "2") (pinfunction "2_2") (pintype "passive"))
      (node (ref "J1") (pin "5") (pinfunction "5_5") (pintype "bidirectional"))
    )
    (net (code "30") (name "Net-(EPD_C6-Pad2)") (class "Default")
      (node (ref "EPD_C6") (pin "2") (pinfunction "2_2") (pintype "passive"))
      (node (ref "J1") (pin "18") (pinfunction "18_18") (pintype "bidirectional"))
    )
    (net (code "31") (name "Net-(EPD_C7-Pad2)") (class "Default")
      (node (ref "EPD_C7") (pin "2") (pinfunction "2_2") (pintype "passive"))
      (node (ref "J1") (pin "19") (pinfunction "19_19") (pintype "bidirectional"))
    )
    (net (code "32") (name "Net-(EPD_C8-Pad2)") (class "Default")
      (node (ref "EPD_C8") (pin "2") (pinfunction "2_2") (pintype "passive"))
      (node (ref "J1") (pin "20") (pinfunction "20_20") (pintype "bidirectional"))
    )
    (net (code "33") (name "Net-(EPD_C10-Pad2)") (class "Default")
      (node (ref "EPD_C10") (pin "2") (pinfunction "2_2") (pintype "passive"))
      (node (ref "J1") (pin "22") (pinfunction "22_22") (pintype "bidirectional"))
    )
    (net (code "34") (name "Net-(EPD_C12-Pad2)") (class "Default")
      (node (ref "EPD_C12") (pin "2") (pinfunction "2_2") (pintype "passive"))
      (node (ref "J1") (pin "24") (pinfunction "24_24") (pintype "bidirectional"))
    )
    (net (code "35") (name "Net-(IC1-CT)") (class "Default")
      (node (ref "C_DELAY") (pin "1") (pinfunction "1_1") (pintype "passive"))
      (node (ref "IC1") (pin "5") (pinfunction "CT_5") (pintype "bidirectional"))
    )
    (net (code "36") (name "Net-(J2-PadA5)") (class "Default")
      (node (ref "J2") (pin "A5") (pinfunction "A5_A5") (pintype "bidirectional"))
      (node (ref "R2-USB1") (pin "2") (pinfunction "2_2") (pintype "passive"))
    )
    (net (code "37") (name "Net-(J2-PadB5)") (class "Default")
      (node (ref "J2") (pin "B5") (pinfunction "B5_B5") (pintype "bidirectional"))
      (node (ref "R2-USB") (pin "1") (pinfunction "1_1") (pintype "passive"))
    )
    (net (code "38") (name "Net-(MCP73831-PROG)") (class "Default")
      (node (ref "MCP73831") (pin "5") (pinfunction "PROG_5") (pintype "input"))
      (node (ref "R2_BAT") (pin "2") (pinfunction "2_2") (pintype "passive"))
    )
    (net (code "39") (name "Net-(MCP73831-STAT)") (class "Default")
      (node (ref "MCP73831") (pin "1") (pinfunction "STAT_1") (pintype "output"))
      (node (ref "R1_BAT") (pin "1") (pinfunction "1_1") (pintype "passive"))
    )
    (net (code "40") (name "PREVGH") (class "Default")
      (node (ref "D5") (pin "1") (pinfunction "K_1") (pintype "bidirectional"))
      (node (ref "EPD_C9") (pin "2") (pinfunction "2_2") (pintype "passive"))
      (node (ref "J1") (pin "21") (pinfunction "21_21") (pintype "bidirectional"))
    )
    (net (code "41") (name "PREVGL") (class "Default")
      (node (ref "D4") (pin "2") (pinfunction "A_2") (pintype "bidirectional"))
      (node (ref "EPD_C11") (pin "2") (pinfunction "2_2") (pintype "passive"))
      (node (ref "J1") (pin "23") (pinfunction "23_23") (pintype "bidirectional"))
    )
    (net (code "42") (name "RESE") (class "Default")
      (node (ref "J1") (pin "3") (pinfunction "3_3") (pintype "bidirectional"))
      (node (ref "Q3") (pin "2") (pinfunction "S_2") (pintype "bidirectional"))
      (node (ref "R3") (pin "1") (pinfunction "1_1") (pintype "passive"))
    )
    (net (code "43") (name "RESE'") (class "Default")
      (node (ref "R2") (pin "2") (pinfunction "2_2") (pintype "passive"))
      (node (ref "R3") (pin "2") (pinfunction "2_2") (pintype "passive"))
      (node (ref "SJ1") (pin "2") (pinfunction "2_2") (pintype "passive"))
    )
    (net (code "44") (name "RESET") (class "Default")
      (node (ref "C5") (pin "1") (pinfunction "1_1") (pintype "passive"))
      (node (ref "IC1") (pin "1") (pinfunction "VOUT_1") (pintype "bidirectional"))
      (node (ref "RESET_BUTTON") (pin "3") (pinfunction "3_3") (pintype "passive"))
      (node (ref "RESET_BUTTON") (pin "4") (pinfunction "4_4") (pintype "passive"))
      (node (ref "R_RESET") (pin "1") (pinfunction "1_1") (pintype "passive"))
      (node (ref "U2") (pin "3") (pinfunction "EN_3") (pintype "input"))
    )
    (net (code "45") (name "RTC_RST") (class "Default")
      (node (ref "U2") (pin "16") (pinfunction "IO18_16") (pintype "bidirectional"))
      (node (ref "U3") (pin "4") (pinfunction "~{RST}_4") (pintype "input"))
    )
    (net (code "46") (name "RX") (class "Default")
      (node (ref "TP2") (pin "TP") (pinfunction "TP_TP") (pintype "input"))
      (node (ref "U2") (pin "24") (pinfunction "RXD0/GPIO17_24") (pintype "bidirectional"))
    )
    (net (code "47") (name "SCK") (class "Default")
      (node (ref "D10") (pin "1") (pinfunction "1_1") (pintype "passive"))
      (node (ref "J1") (pin "13") (pinfunction "13_13") (pintype "bidirectional"))
      (node (ref "J4") (pin "P5") (pinfunction "CLK_P5") (pintype "bidirectional"))
      (node (ref "R6") (pin "1") (pinfunction "1_1") (pintype "passive"))
      (node (ref "TP8") (pin "TP") (pinfunction "TP_TP") (pintype "input"))
      (node (ref "U1") (pin "6") (pinfunction "CLK_6") (pintype "input"))
      (node (ref "U2") (pin "6") (pinfunction "IO6_6") (pintype "bidirectional"))
    )
    (net (code "48") (name "SCL") (class "Default")
      (node (ref "J3") (pin "4") (pinfunction "4_4") (pintype "passive"))
      (node (ref "R2-PINH") (pin "1") (pinfunction "1_1") (pintype "passive"))
      (node (ref "SENSOR2") (pin "4") (pinfunction "SCK_4") (pintype "input"))
      (node (ref "U2") (pin "20") (pinfunction "IO22_20") (pintype "bidirectional"))
      (node (ref "U3") (pin "16") (pinfunction "SCL_16") (pintype "input"))
      (node (ref "U4") (pin "7") (pinfunction "SCL_7") (pintype "input"))
    )
    (net (code "49") (name "SDA") (class "Default")
      (node (ref "J3") (pin "3") (pinfunction "3_3") (pintype "passive"))
      (node (ref "R1_PINH") (pin "1") (pinfunction "1_1") (pintype "passive"))
      (node (ref "SENSOR2") (pin "3") (pinfunction "SDI_3") (pintype "bidirectional"))
      (node (ref "U2") (pin "19") (pinfunction "IO21_19") (pintype "bidirectional"))
      (node (ref "U3") (pin "15") (pinfunction "SDA_15") (pintype "bidirectional"))
      (node (ref "U4") (pin "8") (pinfunction "SDA_8") (pintype "bidirectional"))
    )
    (net (code "50") (name "SRC") (class "Default")
      (node (ref "C4") (pin "2") (pinfunction "2_2") (pintype "passive"))
      (node (ref "D5") (pin "2") (pinfunction "A_2") (pintype "bidirectional"))
      (node (ref "L1") (pin "1") (pinfunction "1_1") (pintype "passive"))
      (node (ref "Q3") (pin "3") (pinfunction "D_3") (pintype "bidirectional"))
    )
    (net (code "51") (name "SS_SD") (class "Default")
      (node (ref "D6") (pin "1") (pinfunction "1_1") (pintype "passive"))
      (node (ref "J4") (pin "P2") (pinfunction "CD/DAT3_P2") (pintype "bidirectional"))
      (node (ref "R10") (pin "1") (pinfunction "1_1") (pintype "passive"))
      (node (ref "U2") (pin "4") (pinfunction "IO4_4") (pintype "bidirectional"))
    )
    (net (code "52") (name "TX") (class "Default")
      (node (ref "TP1") (pin "TP") (pinfunction "TP_TP") (pintype "input"))
      (node (ref "U2") (pin "25") (pinfunction "TXD0/GPIO16_25") (pintype "bidirectional"))
    )
    (net (code "53") (name "USB_D+") (class "Default")
      (node (ref "D1") (pin "1") (pinfunction "I/O1_1_1") (pintype "bidirectional"))
      (node (ref "U2") (pin "14") (pinfunction "IO13_14") (pintype "bidirectional"))
    )
    (net (code "54") (name "USB_D-") (class "Default")
      (node (ref "D1") (pin "3") (pinfunction "I/O2_1_3") (pintype "bidirectional"))
      (node (ref "U2") (pin "13") (pinfunction "IO12_13") (pintype "bidirectional"))
    )
    (net (code "55") (name "VBAT") (class "Default")
      (node (ref "C2_BAT") (pin "1") (pinfunction "1_1") (pintype "passive"))
      (node (ref "MCP73831") (pin "3") (pinfunction "VBAT_3") (pintype "power_in"))
      (node (ref "Q1") (pin "3") (pinfunction "D_3") (pintype "bidirectional"))
      (node (ref "TP3") (pin "TP") (pinfunction "TP_TP") (pintype "input"))
      (node (ref "U4") (pin "2") (pinfunction "CELL_2") (pintype "power_in"))
      (node (ref "U4") (pin "3") (pinfunction "VDD_3") (pintype "power_in"))
    )
    (net (code "56") (name "VBUS") (class "Default")
      (node (ref "C1_BAT") (pin "1") (pinfunction "1_1") (pintype "passive"))
      (node (ref "C4_USB") (pin "1") (pinfunction "1_1") (pintype "passive"))
      (node (ref "C5_USB") (pin "1") (pinfunction "1_1") (pintype "passive"))
      (node (ref "CHG_LED") (pin "A") (pinfunction "A_A") (pintype "passive"))
      (node (ref "D1") (pin "5") (pinfunction "VBUS_5") (pintype "bidirectional"))
      (node (ref "D2") (pin "2") (pinfunction "ANODE_2") (pintype "bidirectional"))
      (node (ref "MCP73831") (pin "4") (pinfunction "VIN_4") (pintype "power_in"))
      (node (ref "PFMF.050.1") (pin "2") (pinfunction "2_2") (pintype "passive"))
      (node (ref "Q1") (pin "1") (pinfunction "G_1") (pintype "bidirectional"))
      (node (ref "R1_PWRUSB") (pin "2") (pinfunction "2_2") (pintype "passive"))
      (node (ref "TP14") (pin "TP") (pinfunction "TP_TP") (pintype "input"))
    )
    (net (code "57") (name "VRTC") (class "Default")
      (node (ref "C10_SUPERCAP") (pin "2") (pinfunction "2_2") (pintype "passive"))
      (node (ref "C8") (pin "1") (pinfunction "1_1") (pintype "passive"))
      (node (ref "R_CAPACITOR") (pin "1") (pinfunction "1_1") (pintype "passive"))
      (node (ref "U3") (pin "14") (pinfunction "VBAT_14") (pintype "power_in"))
    )
    (net (code "58") (name "VUSB") (class "Default")
      (node (ref "J2") (pin "A4") (pinfunction "A4_A4") (pintype "bidirectional"))
      (node (ref "J2") (pin "A9") (pinfunction "A9_A9") (pintype "bidirectional"))
      (node (ref "J2") (pin "B4") (pinfunction "B4_B4") (pintype "bidirectional"))
      (node (ref "J2") (pin "B9") (pinfunction "B9_B9") (pintype "bidirectional"))
      (node (ref "PFMF.050.1") (pin "1") (pinfunction "1_1") (pintype "passive"))
    )
    (net (code "59") (name "unconnected-(IC1-NC-Pad4)") (class "Default")
      (node (ref "IC1") (pin "4") (pinfunction "NC_4") (pintype "no_connect"))
    )
    (net (code "60") (name "unconnected-(IC1-VDD-Pad2)") (class "Default")
      (node (ref "IC1") (pin "2") (pinfunction "VDD_2") (pintype "bidirectional"))
    )
    (net (code "61") (name "unconnected-(IC4-NC-Pad4)") (class "Default")
      (node (ref "IC4") (pin "4") (pinfunction "NC_4") (pintype "no_connect"))
    )
    (net (code "62") (name "unconnected-(J1-Pad1)") (class "Default")
      (node (ref "J1") (pin "1") (pinfunction "1_1") (pintype "bidirectional"))
    )
    (net (code "63") (name "unconnected-(J1-Pad6)") (class "Default")
      (node (ref "J1") (pin "6") (pinfunction "6_6") (pintype "bidirectional"))
    )
    (net (code "64") (name "unconnected-(J1-Pad7)") (class "Default")
      (node (ref "J1") (pin "7") (pinfunction "7_7") (pintype "bidirectional"))
    )
    (net (code "65") (name "unconnected-(J2-PadA8)") (class "Default")
      (node (ref "J2") (pin "A8") (pinfunction "A8_A8") (pintype "bidirectional"))
    )
    (net (code "66") (name "unconnected-(J2-PadB8)") (class "Default")
      (node (ref "J2") (pin "B8") (pinfunction "B8_B8") (pintype "bidirectional"))
    )
    (net (code "67") (name "unconnected-(J4-DAT1-PadP8)") (class "Default")
      (node (ref "J4") (pin "P8") (pinfunction "DAT1_P8") (pintype "bidirectional"))
    )
    (net (code "68") (name "unconnected-(J4-DAT2-PadP1)") (class "Default")
      (node (ref "J4") (pin "P1") (pinfunction "DAT2_P1") (pintype "bidirectional"))
    )
    (net (code "69") (name "unconnected-(J4-DETECTION_1-PadS1)") (class "Default")
      (node (ref "J4") (pin "S1") (pinfunction "DETECTION_1_S1") (pintype "bidirectional"))
    )
    (net (code "70") (name "unconnected-(J4-DETECTION_2-PadS2)") (class "Default")
      (node (ref "J4") (pin "S2") (pinfunction "DETECTION_2_S2") (pintype "bidirectional"))
    )
    (net (code "71") (name "unconnected-(U2-NC-Pad22)") (class "Default")
      (node (ref "U2") (pin "22") (pinfunction "NC_22") (pintype "no_connect"))
    )
    (net (code "72") (name "unconnected-(U4-~{ALERT}-Pad5)") (class "Default")
      (node (ref "U4") (pin "5") (pinfunction "~{ALERT}_5") (pintype "output"))
    )
  )
)
